# molecule.net
KiCad netlist of a schematic drawn in Altium Designer
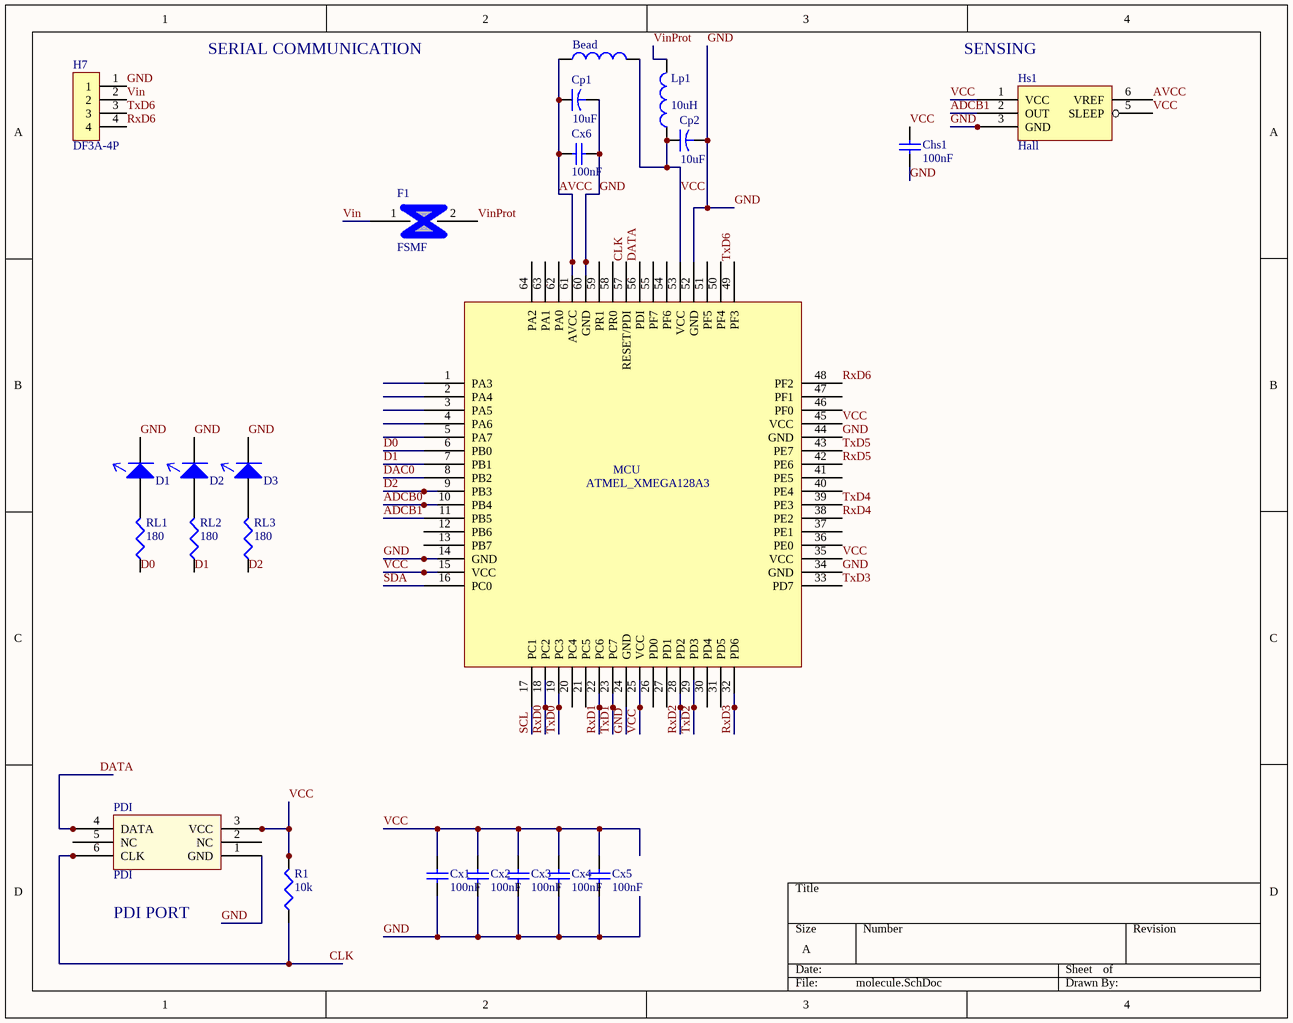
[diagram p0: molecule.SchDoc]

(export (version "E")
  (design (tool "Eeschema 10.0.6"))
  (components
    (comp (ref "Bead")
      (value "~")
      (footprint "C0402-DRL")
      (description "Inductor")
      (fields (field (name "PUBLISHER") "Altium Limited"))
      (libsource (lib "Miscellaneous Devices") (part "Inductor"))
    )
    (comp (ref "Chs1")
      (value "100nF")
      (footprint "C0402-DRL")
      (description "Capacitor")
      (fields (field (name "PUBLISHER") "Altium Limited"))
      (libsource (lib "Miscellaneous Devices") (part "Cap"))
    )
    (comp (ref "Cp1")
      (value "10uF")
      (footprint "C0603-DRL")
      (description "Capacitor")
      (fields (field (name "PUBLISHER") "Altium Limited"))
      (libsource (lib "Miscellaneous Devices") (part "Cap2"))
    )
    (comp (ref "Cp2")
      (value "10uF")
      (footprint "C0603-DRL")
      (description "Capacitor")
      (fields (field (name "PUBLISHER") "Altium Limited"))
      (libsource (lib "Miscellaneous Devices") (part "Cap2"))
    )
    (comp (ref "Cx1")
      (value "100nF")
      (footprint "C0402-DRL")
      (description "Capacitor")
      (fields (field (name "PUBLISHER") "Altium Limited"))
      (libsource (lib "Miscellaneous Devices") (part "Cap"))
    )
    (comp (ref "Cx2")
      (value "100nF")
      (footprint "C0402-DRL")
      (description "Capacitor")
      (fields (field (name "PUBLISHER") "Altium Limited"))
      (libsource (lib "Miscellaneous Devices") (part "Cap"))
    )
    (comp (ref "Cx3")
      (value "100nF")
      (footprint "C0402-DRL")
      (description "Capacitor")
      (fields (field (name "PUBLISHER") "Altium Limited"))
      (libsource (lib "Miscellaneous Devices") (part "Cap"))
    )
    (comp (ref "Cx4")
      (value "100nF")
      (footprint "C0402-DRL")
      (description "Capacitor")
      (fields (field (name "PUBLISHER") "Altium Limited"))
      (libsource (lib "Miscellaneous Devices") (part "Cap"))
    )
    (comp (ref "Cx5")
      (value "100nF")
      (footprint "C0402-DRL")
      (description "Capacitor")
      (fields (field (name "PUBLISHER") "Altium Limited"))
      (libsource (lib "Miscellaneous Devices") (part "Cap"))
    )
    (comp (ref "Cx6")
      (value "100nF")
      (footprint "C0402-DRL")
      (description "Capacitor")
      (fields (field (name "PUBLISHER") "Altium Limited"))
      (libsource (lib "Miscellaneous Devices") (part "Cap"))
    )
    (comp (ref "D1")
      (value "LEDSMD")
      (footprint "D1206-DRL")
      (description "LED")
      (libsource (lib "test1") (part "LEDSMD"))
    )
    (comp (ref "D2")
      (value "LEDSMD")
      (footprint "D1206-DRL")
      (description "LED")
      (libsource (lib "test1") (part "LEDSMD"))
    )
    (comp (ref "D3")
      (value "LEDSMD")
      (footprint "D1206-DRL")
      (description "LED")
      (libsource (lib "test1") (part "LEDSMD"))
    )
    (comp (ref "F1")
      (value "FSMF")
      (footprint "C0603-DRL")
      (description "Fuse PTC Reset")
      (libsource (lib "test1") (part "FSMF"))
    )
    (comp (ref "H7")
      (value "DF3A-4P")
      (footprint "UART")
      (description "4pin header")
      (libsource (lib "hirose") (part "DF3A-4P"))
    )
    (comp (ref "Hs1")
      (value "Hall")
      (footprint "HALL")
      (description "620-11-ND Hall Effect")
      (libsource (lib "ss") (part "Hall"))
    )
    (comp (ref "Lp1")
      (value "10uH")
      (footprint "C0603-DRL")
      (description "Inductor")
      (fields (field (name "PUBLISHER") "Altium Limited"))
      (libsource (lib "Miscellaneous Devices") (part "Inductor"))
    )
    (comp (ref "MCU")
      (value "ATMEL_XMEGA128A3")
      (footprint "QFN50P900X900X100-64N")
      (libsource (lib "atmel") (part "ATMEL_XMEGA128"))
    )
    (comp (ref "PDI") (value "PDI") (footprint "PDI_SMT") (libsource (lib "atmel") (part "PDI")))
    (comp (ref "R1")
      (value "10k")
      (footprint "R0402-DRL")
      (description "Resistor")
      (fields (field (name "Comment") "R") (field (name "PUBLISHER") "Altium Limited"))
      (libsource (lib "standard") (part "R"))
    )
    (comp (ref "RL1")
      (value "180")
      (footprint "R0402-DRL")
      (description "Resistor")
      (fields (field (name "Comment") "R") (field (name "PUBLISHER") "Altium Limited"))
      (libsource (lib "standard") (part "R"))
    )
    (comp (ref "RL2")
      (value "180")
      (footprint "R0402-DRL")
      (description "Resistor")
      (fields (field (name "Comment") "R") (field (name "PUBLISHER") "Altium Limited"))
      (libsource (lib "standard") (part "R"))
    )
    (comp (ref "RL3")
      (value "180")
      (footprint "R0402-DRL")
      (description "Resistor")
      (fields (field (name "Comment") "R") (field (name "PUBLISHER") "Altium Limited"))
      (libsource (lib "standard") (part "R"))
    )
  )
  (nets
    (net (code "1") (name "/ADCB0") (class "Default")
      (node (ref "MCU") (pin "10") (pinfunction "PB4_10") (pintype "passive"))
    )
    (net (code "2") (name "/ADCB1") (class "Default")
      (node (ref "Hs1") (pin "2") (pinfunction "OUT_2") (pintype "passive"))
      (node (ref "MCU") (pin "11") (pinfunction "PB5_11") (pintype "passive"))
    )
    (net (code "3") (name "/AVCC") (class "Default")
      (node (ref "Bead") (pin "1") (pinfunction "1_1") (pintype "passive"))
      (node (ref "Cp1") (pin "1") (pinfunction "1_1") (pintype "passive"))
      (node (ref "Cx6") (pin "2") (pinfunction "2_2") (pintype "passive"))
      (node (ref "Hs1") (pin "6") (pinfunction "VREF_6") (pintype "passive"))
      (node (ref "MCU") (pin "61") (pinfunction "AVCC_61") (pintype "passive"))
    )
    (net (code "4") (name "/CLK") (class "Default")
      (node (ref "MCU") (pin "57") (pinfunction "RESET/PDI_57") (pintype "passive"))
      (node (ref "PDI") (pin "6") (pinfunction "CLK_6") (pintype "passive"))
      (node (ref "R1") (pin "1") (pinfunction "1_1") (pintype "passive"))
    )
    (net (code "5") (name "/D0") (class "Default")
      (node (ref "MCU") (pin "6") (pinfunction "PB0_6") (pintype "passive"))
      (node (ref "RL1") (pin "1") (pinfunction "1_1") (pintype "passive"))
    )
    (net (code "6") (name "/D1") (class "Default")
      (node (ref "MCU") (pin "7") (pinfunction "PB1_7") (pintype "passive"))
      (node (ref "RL2") (pin "1") (pinfunction "1_1") (pintype "passive"))
    )
    (net (code "7") (name "/D2") (class "Default")
      (node (ref "MCU") (pin "9") (pinfunction "PB3_9") (pintype "passive"))
      (node (ref "RL3") (pin "1") (pinfunction "1_1") (pintype "passive"))
    )
    (net (code "8") (name "/DAC0") (class "Default")
      (node (ref "MCU") (pin "8") (pinfunction "PB2_8") (pintype "passive"))
    )
    (net (code "9") (name "/DATA") (class "Default")
      (node (ref "MCU") (pin "56") (pinfunction "PDI_56") (pintype "passive"))
      (node (ref "PDI") (pin "4") (pinfunction "DATA_4") (pintype "passive"))
    )
    (net (code "10") (name "/GND") (class "Default")
      (node (ref "Chs1") (pin "1") (pinfunction "1_1") (pintype "passive"))
      (node (ref "Cp1") (pin "2") (pinfunction "2_2") (pintype "passive"))
      (node (ref "Cp2") (pin "2") (pinfunction "2_2") (pintype "passive"))
      (node (ref "Cx1") (pin "1") (pinfunction "1_1") (pintype "passive"))
      (node (ref "Cx2") (pin "1") (pinfunction "1_1") (pintype "passive"))
      (node (ref "Cx3") (pin "1") (pinfunction "1_1") (pintype "passive"))
      (node (ref "Cx4") (pin "1") (pinfunction "1_1") (pintype "passive"))
      (node (ref "Cx5") (pin "1") (pinfunction "1_1") (pintype "passive"))
      (node (ref "Cx6") (pin "1") (pinfunction "1_1") (pintype "passive"))
      (node (ref "D1") (pin "1") (pinfunction "K_1") (pintype "passive"))
      (node (ref "D2") (pin "1") (pinfunction "K_1") (pintype "passive"))
      (node (ref "D3") (pin "1") (pinfunction "K_1") (pintype "passive"))
      (node (ref "H7") (pin "1") (pinfunction "1_1") (pintype "passive"))
      (node (ref "Hs1") (pin "3") (pinfunction "GND_3") (pintype "passive"))
      (node (ref "MCU") (pin "14") (pinfunction "GND_14") (pintype "passive"))
      (node (ref "MCU") (pin "24") (pinfunction "GND_24") (pintype "passive"))
      (node (ref "MCU") (pin "34") (pinfunction "GND_34") (pintype "passive"))
      (node (ref "MCU") (pin "44") (pinfunction "GND_44") (pintype "passive"))
      (node (ref "MCU") (pin "52") (pinfunction "GND_52") (pintype "passive"))
      (node (ref "MCU") (pin "60") (pinfunction "GND_60") (pintype "passive"))
      (node (ref "PDI") (pin "1") (pinfunction "GND_1") (pintype "passive"))
    )
    (net (code "11") (name "/RxD0") (class "Default")
      (node (ref "MCU") (pin "18") (pinfunction "PC2_18") (pintype "passive"))
    )
    (net (code "12") (name "/RxD1") (class "Default")
      (node (ref "MCU") (pin "22") (pinfunction "PC6_22") (pintype "passive"))
    )
    (net (code "13") (name "/RxD2") (class "Default")
      (node (ref "MCU") (pin "28") (pinfunction "PD2_28") (pintype "passive"))
    )
    (net (code "14") (name "/RxD3") (class "Default")
      (node (ref "MCU") (pin "32") (pinfunction "PD6_32") (pintype "passive"))
    )
    (net (code "15") (name "/RxD4") (class "Default")
      (node (ref "MCU") (pin "38") (pinfunction "PE2_38") (pintype "passive"))
    )
    (net (code "16") (name "/RxD5") (class "Default")
      (node (ref "MCU") (pin "42") (pinfunction "PE6_42") (pintype "passive"))
    )
    (net (code "17") (name "/RxD6") (class "Default")
      (node (ref "H7") (pin "4") (pinfunction "4_4") (pintype "passive"))
      (node (ref "MCU") (pin "48") (pinfunction "PF2_48") (pintype "passive"))
    )
    (net (code "18") (name "/SCL") (class "Default")
      (node (ref "MCU") (pin "17") (pinfunction "PC1_17") (pintype "passive"))
    )
    (net (code "19") (name "/SDA") (class "Default")
      (node (ref "MCU") (pin "16") (pinfunction "PC0_16") (pintype "passive"))
    )
    (net (code "20") (name "/TxD0") (class "Default")
      (node (ref "MCU") (pin "19") (pinfunction "PC3_19") (pintype "passive"))
    )
    (net (code "21") (name "/TxD1") (class "Default")
      (node (ref "MCU") (pin "23") (pinfunction "PC7_23") (pintype "passive"))
    )
    (net (code "22") (name "/TxD2") (class "Default")
      (node (ref "MCU") (pin "29") (pinfunction "PD3_29") (pintype "passive"))
    )
    (net (code "23") (name "/TxD3") (class "Default")
      (node (ref "MCU") (pin "33") (pinfunction "PD7_33") (pintype "passive"))
    )
    (net (code "24") (name "/TxD4") (class "Default")
      (node (ref "MCU") (pin "39") (pinfunction "PE3_39") (pintype "passive"))
    )
    (net (code "25") (name "/TxD5") (class "Default")
      (node (ref "MCU") (pin "43") (pinfunction "PE7_43") (pintype "passive"))
    )
    (net (code "26") (name "/TxD6") (class "Default")
      (node (ref "H7") (pin "3") (pinfunction "3_3") (pintype "passive"))
      (node (ref "MCU") (pin "49") (pinfunction "PF3_49") (pintype "passive"))
    )
    (net (code "27") (name "/VCC") (class "Default")
      (node (ref "Bead") (pin "2") (pinfunction "2_2") (pintype "passive"))
      (node (ref "Chs1") (pin "2") (pinfunction "2_2") (pintype "passive"))
      (node (ref "Cp2") (pin "1") (pinfunction "1_1") (pintype "passive"))
      (node (ref "Cx1") (pin "2") (pinfunction "2_2") (pintype "passive"))
      (node (ref "Cx2") (pin "2") (pinfunction "2_2") (pintype "passive"))
      (node (ref "Cx3") (pin "2") (pinfunction "2_2") (pintype "passive"))
      (node (ref "Cx4") (pin "2") (pinfunction "2_2") (pintype "passive"))
      (node (ref "Cx5") (pin "2") (pinfunction "2_2") (pintype "passive"))
      (node (ref "Hs1") (pin "1") (pinfunction "VCC_1") (pintype "passive"))
      (node (ref "Hs1") (pin "5") (pinfunction "SLEEP_5") (pintype "passive"))
      (node (ref "Lp1") (pin "1") (pinfunction "1_1") (pintype "passive"))
      (node (ref "MCU") (pin "15") (pinfunction "VCC_15") (pintype "passive"))
      (node (ref "MCU") (pin "25") (pinfunction "VCC_25") (pintype "passive"))
      (node (ref "MCU") (pin "35") (pinfunction "VCC_35") (pintype "passive"))
      (node (ref "MCU") (pin "45") (pinfunction "VCC_45") (pintype "passive"))
      (node (ref "MCU") (pin "53") (pinfunction "VCC_53") (pintype "passive"))
      (node (ref "PDI") (pin "3") (pinfunction "VCC_3") (pintype "passive"))
      (node (ref "R1") (pin "2") (pinfunction "2_2") (pintype "passive"))
    )
    (net (code "28") (name "/Vin") (class "Default")
      (node (ref "F1") (pin "1") (pinfunction "1_1") (pintype "passive"))
      (node (ref "H7") (pin "2") (pinfunction "2_2") (pintype "passive"))
    )
    (net (code "29") (name "/VinProt") (class "Default")
      (node (ref "F1") (pin "2") (pinfunction "2_2") (pintype "passive"))
      (node (ref "Lp1") (pin "2") (pinfunction "2_2") (pintype "passive"))
    )
    (net (code "30") (name "Net-(D1-A)") (class "Default")
      (node (ref "D1") (pin "2") (pinfunction "A_2") (pintype "passive"))
      (node (ref "RL1") (pin "2") (pinfunction "2_2") (pintype "passive"))
    )
    (net (code "31") (name "Net-(D2-A)") (class "Default")
      (node (ref "D2") (pin "2") (pinfunction "A_2") (pintype "passive"))
      (node (ref "RL2") (pin "2") (pinfunction "2_2") (pintype "passive"))
    )
    (net (code "32") (name "Net-(D3-A)") (class "Default")
      (node (ref "D3") (pin "2") (pinfunction "A_2") (pintype "passive"))
      (node (ref "RL3") (pin "2") (pinfunction "2_2") (pintype "passive"))
    )
    (net (code "33") (name "unconnected-(MCU-PA0-Pad62)") (class "Default")
      (node (ref "MCU") (pin "62") (pinfunction "PA0_62") (pintype "passive"))
    )
    (net (code "34") (name "unconnected-(MCU-PA1-Pad63)") (class "Default")
      (node (ref "MCU") (pin "63") (pinfunction "PA1_63") (pintype "passive"))
    )
    (net (code "35") (name "unconnected-(MCU-PA2-Pad64)") (class "Default")
      (node (ref "MCU") (pin "64") (pinfunction "PA2_64") (pintype "passive"))
    )
    (net (code "36") (name "unconnected-(MCU-PA3-Pad1)") (class "Default")
      (node (ref "MCU") (pin "1") (pinfunction "PA3_1") (pintype "passive"))
    )
    (net (code "37") (name "unconnected-(MCU-PA4-Pad2)") (class "Default")
      (node (ref "MCU") (pin "2") (pinfunction "PA4_2") (pintype "passive"))
    )
    (net (code "38") (name "unconnected-(MCU-PA5-Pad3)") (class "Default")
      (node (ref "MCU") (pin "3") (pinfunction "PA5_3") (pintype "passive"))
    )
    (net (code "39") (name "unconnected-(MCU-PA6-Pad4)") (class "Default")
      (node (ref "MCU") (pin "4") (pinfunction "PA6_4") (pintype "passive"))
    )
    (net (code "40") (name "unconnected-(MCU-PA7-Pad5)") (class "Default")
      (node (ref "MCU") (pin "5") (pinfunction "PA7_5") (pintype "passive"))
    )
    (net (code "41") (name "unconnected-(MCU-PB6-Pad12)") (class "Default")
      (node (ref "MCU") (pin "12") (pinfunction "PB6_12") (pintype "passive"))
    )
    (net (code "42") (name "unconnected-(MCU-PB7-Pad13)") (class "Default")
      (node (ref "MCU") (pin "13") (pinfunction "PB7_13") (pintype "passive"))
    )
    (net (code "43") (name "unconnected-(MCU-PC4-Pad20)") (class "Default")
      (node (ref "MCU") (pin "20") (pinfunction "PC4_20") (pintype "passive"))
    )
    (net (code "44") (name "unconnected-(MCU-PC5-Pad21)") (class "Default")
      (node (ref "MCU") (pin "21") (pinfunction "PC5_21") (pintype "passive"))
    )
    (net (code "45") (name "unconnected-(MCU-PD0-Pad26)") (class "Default")
      (node (ref "MCU") (pin "26") (pinfunction "PD0_26") (pintype "passive"))
    )
    (net (code "46") (name "unconnected-(MCU-PD1-Pad27)") (class "Default")
      (node (ref "MCU") (pin "27") (pinfunction "PD1_27") (pintype "passive"))
    )
    (net (code "47") (name "unconnected-(MCU-PD4-Pad30)") (class "Default")
      (node (ref "MCU") (pin "30") (pinfunction "PD4_30") (pintype "passive"))
    )
    (net (code "48") (name "unconnected-(MCU-PD5-Pad31)") (class "Default")
      (node (ref "MCU") (pin "31") (pinfunction "PD5_31") (pintype "passive"))
    )
    (net (code "49") (name "unconnected-(MCU-PE0-Pad36)") (class "Default")
      (node (ref "MCU") (pin "36") (pinfunction "PE0_36") (pintype "passive"))
    )
    (net (code "50") (name "unconnected-(MCU-PE1-Pad37)") (class "Default")
      (node (ref "MCU") (pin "37") (pinfunction "PE1_37") (pintype "passive"))
    )
    (net (code "51") (name "unconnected-(MCU-PE4-Pad40)") (class "Default")
      (node (ref "MCU") (pin "40") (pinfunction "PE4_40") (pintype "passive"))
    )
    (net (code "52") (name "unconnected-(MCU-PE5-Pad41)") (class "Default")
      (node (ref "MCU") (pin "41") (pinfunction "PE5_41") (pintype "passive"))
    )
    (net (code "53") (name "unconnected-(MCU-PF0-Pad46)") (class "Default")
      (node (ref "MCU") (pin "46") (pinfunction "PF0_46") (pintype "passive"))
    )
    (net (code "54") (name "unconnected-(MCU-PF1-Pad47)") (class "Default")
      (node (ref "MCU") (pin "47") (pinfunction "PF1_47") (pintype "passive"))
    )
    (net (code "55") (name "unconnected-(MCU-PF4-Pad50)") (class "Default")
      (node (ref "MCU") (pin "50") (pinfunction "PF4_50") (pintype "passive"))
    )
    (net (code "56") (name "unconnected-(MCU-PF5-Pad51)") (class "Default")
      (node (ref "MCU") (pin "51") (pinfunction "PF5_51") (pintype "passive"))
    )
    (net (code "57") (name "unconnected-(MCU-PF6-Pad54)") (class "Default")
      (node (ref "MCU") (pin "54") (pinfunction "PF6_54") (pintype "passive"))
    )
    (net (code "58") (name "unconnected-(MCU-PF7-Pad55)") (class "Default")
      (node (ref "MCU") (pin "55") (pinfunction "PF7_55") (pintype "passive"))
    )
    (net (code "59") (name "unconnected-(MCU-PR0-Pad58)") (class "Default")
      (node (ref "MCU") (pin "58") (pinfunction "PR0_58") (pintype "passive"))
    )
    (net (code "60") (name "unconnected-(MCU-PR1-Pad59)") (class "Default")
      (node (ref "MCU") (pin "59") (pinfunction "PR1_59") (pintype "passive"))
    )
    (net (code "61") (name "unconnected-(PDI-NC-Pad2)") (class "Default")
      (node (ref "PDI") (pin "2") (pinfunction "NC_2") (pintype "passive"))
    )
    (net (code "62") (name "unconnected-(PDI-NC-Pad5)") (class "Default")
      (node (ref "PDI") (pin "5") (pinfunction "NC_5") (pintype "passive"))
    )
  )
)
